# Miscellaneous.net
KiCad netlist of a schematic drawn in Altium Designer
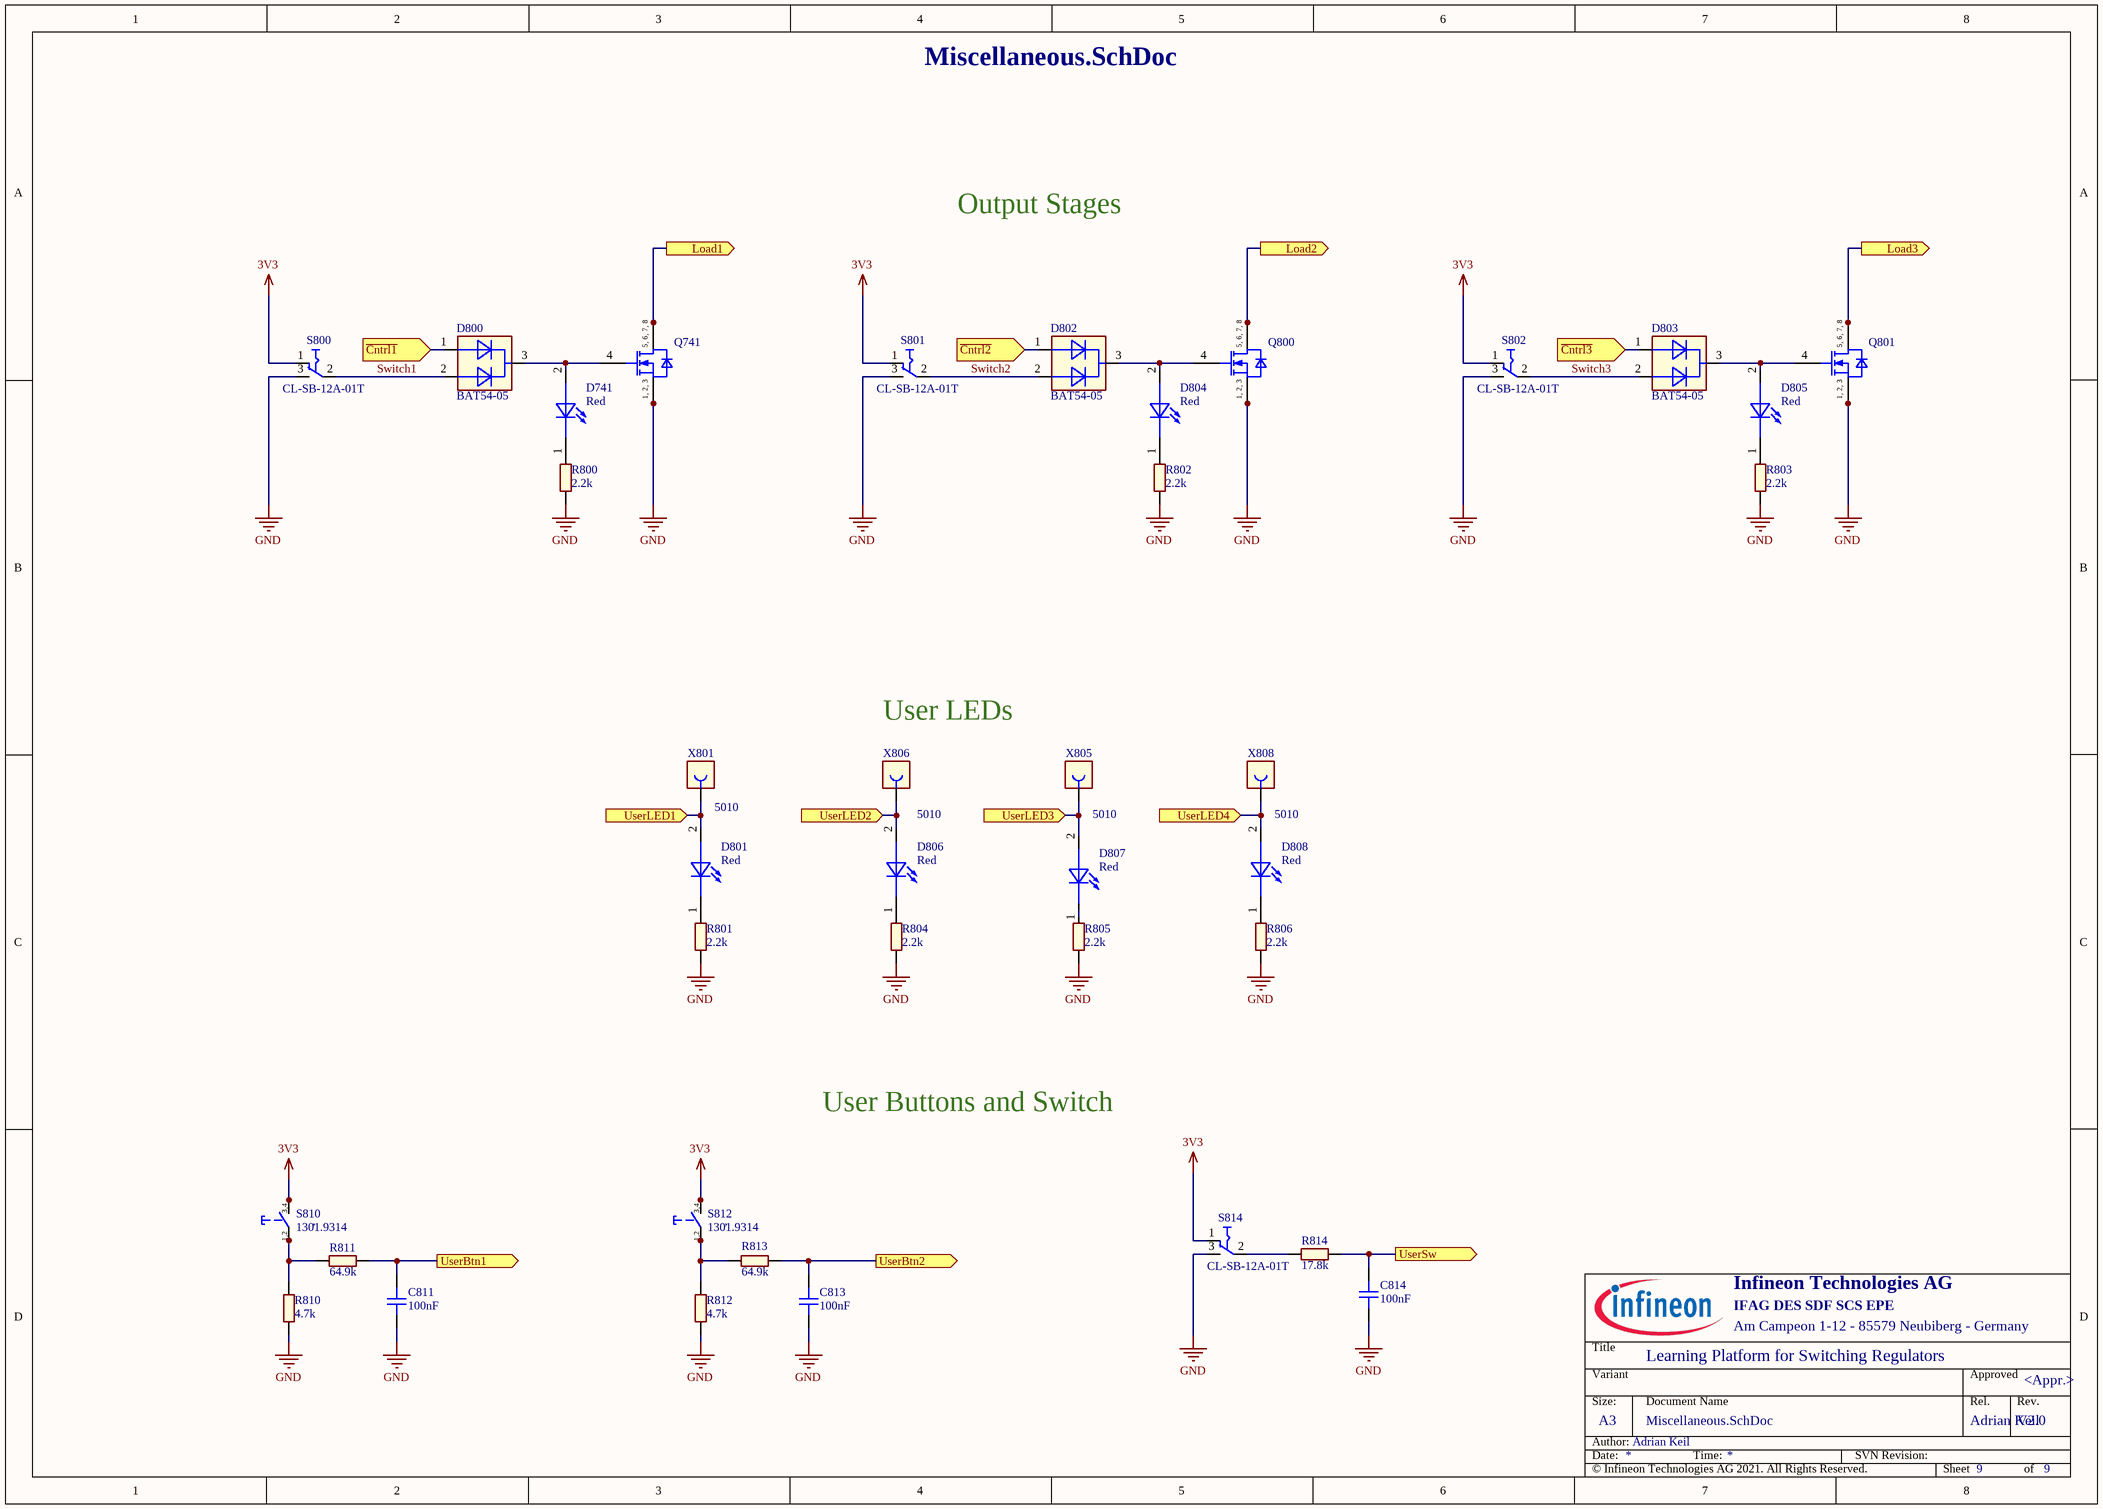
[diagram p0: Miscellaneous.SchDoc]

(export (version "E")
  (design (tool "Eeschema 10.0.6"))
  (components
    (comp (ref "C811")
      (value "100nF")
      (footprint "CAPC1608X90N-2")
      (description "CAP / CERA / 100nF / 50V / 10% / X7R (EIA) / -55°C to 125°C / 0603 / SMD / -")
      (fields (field (name "MANUFACTURER") "AVX"))
      (libsource (lib "PCBLibraryData") (part "CAP-SGL-STD-02P_00000001"))
    )
    (comp (ref "C813")
      (value "100nF")
      (footprint "CAPC1608X90N-2")
      (description "CAP / CERA / 100nF / 50V / 10% / X7R (EIA) / -55°C to 125°C / 0603 / SMD / -")
      (fields (field (name "MANUFACTURER") "AVX"))
      (libsource (lib "PCBLibraryData") (part "CAP-SGL-STD-02P_00000001"))
    )
    (comp (ref "C814")
      (value "100nF")
      (footprint "CAPC1608X90N-2")
      (description "CAP / CERA / 100nF / 50V / 10% / X7R (EIA) / -55°C to 125°C / 0603 / SMD / -")
      (fields (field (name "MANUFACTURER") "AVX"))
      (libsource (lib "PCBLibraryData") (part "CAP-SGL-STD-02P_00000001"))
    )
    (comp (ref "D741")
      (value "Red")
      (footprint "LEDSC160X80X80-2N-1")
      (description "WL-SMCW SMT Mono-color Chip LED Waterclear, Red,630nm")
      (fields (field (name "MANUFACTURER") "Wurth Elektronik"))
      (libsource (lib "PCBLibraryData") (part "d_led_a"))
    )
    (comp (ref "D800")
      (value "BAT54-05")
      (footprint "SOT95P240X110-3N-1-V")
      (description "Silicon Schottky Diode, LS(nH) 1.8, VR 30V")
      (fields
        (field (name "LEGACY PARTNUMBER") "IFX01401370")
        (field (name "MANUFACTURER") "Infineon Technologies")
      )
      (libsource (lib "PCBLibraryData") (part "d_dual_a1a2c3_3p"))
    )
    (comp (ref "D801")
      (value "Red")
      (footprint "LEDSC160X80X80-2N-1")
      (description "WL-SMCW SMT Mono-color Chip LED Waterclear, Red,630nm")
      (fields (field (name "MANUFACTURER") "Wurth Elektronik"))
      (libsource (lib "PCBLibraryData") (part "d_led_a"))
    )
    (comp (ref "D802")
      (value "BAT54-05")
      (footprint "SOT95P240X110-3N-1-V")
      (description "Silicon Schottky Diode, LS(nH) 1.8, VR 30V")
      (fields
        (field (name "LEGACY PARTNUMBER") "IFX01401370")
        (field (name "MANUFACTURER") "Infineon Technologies")
      )
      (libsource (lib "PCBLibraryData") (part "d_dual_a1a2c3_3p"))
    )
    (comp (ref "D803")
      (value "BAT54-05")
      (footprint "SOT95P240X110-3N-1-V")
      (description "Silicon Schottky Diode, LS(nH) 1.8, VR 30V")
      (fields
        (field (name "LEGACY PARTNUMBER") "IFX01401370")
        (field (name "MANUFACTURER") "Infineon Technologies")
      )
      (libsource (lib "PCBLibraryData") (part "d_dual_a1a2c3_3p"))
    )
    (comp (ref "D804")
      (value "Red")
      (footprint "LEDSC160X80X80-2N-1")
      (description "WL-SMCW SMT Mono-color Chip LED Waterclear, Red,630nm")
      (fields (field (name "MANUFACTURER") "Wurth Elektronik"))
      (libsource (lib "PCBLibraryData") (part "d_led_a"))
    )
    (comp (ref "D805")
      (value "Red")
      (footprint "LEDSC160X80X80-2N-1")
      (description "WL-SMCW SMT Mono-color Chip LED Waterclear, Red,630nm")
      (fields (field (name "MANUFACTURER") "Wurth Elektronik"))
      (libsource (lib "PCBLibraryData") (part "d_led_a"))
    )
    (comp (ref "D806")
      (value "Red")
      (footprint "LEDSC160X80X80-2N-1")
      (description "WL-SMCW SMT Mono-color Chip LED Waterclear, Red,630nm")
      (fields (field (name "MANUFACTURER") "Wurth Elektronik"))
      (libsource (lib "PCBLibraryData") (part "d_led_a"))
    )
    (comp (ref "D807")
      (value "Red")
      (footprint "LEDSC160X80X80-2N-1")
      (description "WL-SMCW SMT Mono-color Chip LED Waterclear, Red,630nm")
      (fields (field (name "MANUFACTURER") "Wurth Elektronik"))
      (libsource (lib "PCBLibraryData") (part "d_led_a"))
    )
    (comp (ref "D808")
      (value "Red")
      (footprint "LEDSC160X80X80-2N-1")
      (description "WL-SMCW SMT Mono-color Chip LED Waterclear, Red,630nm")
      (fields (field (name "MANUFACTURER") "Wurth Elektronik"))
      (libsource (lib "PCBLibraryData") (part "d_led_a"))
    )
    (comp (ref "Q741")
      (value "igfet_n_ch_enh_dio_1s2s3s4g5d6d7d8d_8p")
      (footprint "IFX-PG-TDSON-8-6-V")
      (description "OptiMOS Power MOSFET, 30V")
      (fields (field (name "MANUFACTURER") "Infineon Technologies"))
      (libsource (lib "PCBLibraryData") (part "igfet_n_ch_enh_dio_1s2s3s4g5d6d7d8d_8p"))
    )
    (comp (ref "Q800")
      (value "igfet_n_ch_enh_dio_1s2s3s4g5d6d7d8d_8p")
      (footprint "IFX-PG-TDSON-8-6-V")
      (description "OptiMOS Power MOSFET, 30V")
      (fields (field (name "MANUFACTURER") "Infineon Technologies"))
      (libsource (lib "PCBLibraryData") (part "igfet_n_ch_enh_dio_1s2s3s4g5d6d7d8d_8p"))
    )
    (comp (ref "Q801")
      (value "igfet_n_ch_enh_dio_1s2s3s4g5d6d7d8d_8p")
      (footprint "IFX-PG-TDSON-8-6-V")
      (description "OptiMOS Power MOSFET, 30V")
      (fields (field (name "MANUFACTURER") "Infineon Technologies"))
      (libsource (lib "PCBLibraryData") (part "igfet_n_ch_enh_dio_1s2s3s4g5d6d7d8d_8p"))
    )
    (comp (ref "R800")
      (value "2.2k")
      (footprint "RESC1609X50N")
      (description "RES / STD / 2.2k / 100mW / 1% / 100ppm/K / -55°C to 155°C / 0603 / SMD / -")
      (fields (field (name "LEGACY PARTNUMBER") "RES01801179") (field (name "MANUFACTURER") "Vishay"))
      (libsource (lib "") (part "RES-SGL-STD-02P_00000006_1"))
    )
    (comp (ref "R801")
      (value "2.2k")
      (footprint "RESC1609X50N")
      (description "RES / STD / 2.2k / 100mW / 1% / 100ppm/K / -55°C to 155°C / 0603 / SMD / -")
      (fields (field (name "LEGACY PARTNUMBER") "RES01801179") (field (name "MANUFACTURER") "Vishay"))
      (libsource (lib "") (part "RES-SGL-STD-02P_00000006_1"))
    )
    (comp (ref "R802")
      (value "2.2k")
      (footprint "RESC1609X50N")
      (description "RES / STD / 2.2k / 100mW / 1% / 100ppm/K / -55°C to 155°C / 0603 / SMD / -")
      (fields (field (name "LEGACY PARTNUMBER") "RES01801179") (field (name "MANUFACTURER") "Vishay"))
      (libsource (lib "") (part "RES-SGL-STD-02P_00000006_1"))
    )
    (comp (ref "R803")
      (value "2.2k")
      (footprint "RESC1609X50N")
      (description "RES / STD / 2.2k / 100mW / 1% / 100ppm/K / -55°C to 155°C / 0603 / SMD / -")
      (fields (field (name "LEGACY PARTNUMBER") "RES01801179") (field (name "MANUFACTURER") "Vishay"))
      (libsource (lib "") (part "RES-SGL-STD-02P_00000006_1"))
    )
    (comp (ref "R804")
      (value "2.2k")
      (footprint "RESC1609X50N")
      (description "RES / STD / 2.2k / 100mW / 1% / 100ppm/K / -55°C to 155°C / 0603 / SMD / -")
      (fields (field (name "LEGACY PARTNUMBER") "RES01801179") (field (name "MANUFACTURER") "Vishay"))
      (libsource (lib "") (part "RES-SGL-STD-02P_00000006_1"))
    )
    (comp (ref "R805")
      (value "2.2k")
      (footprint "RESC1609X50N")
      (description "RES / STD / 2.2k / 100mW / 1% / 100ppm/K / -55°C to 155°C / 0603 / SMD / -")
      (fields (field (name "LEGACY PARTNUMBER") "RES01801179") (field (name "MANUFACTURER") "Vishay"))
      (libsource (lib "") (part "RES-SGL-STD-02P_00000006_1"))
    )
    (comp (ref "R806")
      (value "2.2k")
      (footprint "RESC1609X50N")
      (description "RES / STD / 2.2k / 100mW / 1% / 100ppm/K / -55°C to 155°C / 0603 / SMD / -")
      (fields (field (name "LEGACY PARTNUMBER") "RES01801179") (field (name "MANUFACTURER") "Vishay"))
      (libsource (lib "") (part "RES-SGL-STD-02P_00000006_1"))
    )
    (comp (ref "R810")
      (value "4.7k")
      (footprint "RESC1609X55N")
      (description "RES / STD / 4.7k / 100mW / 1% / 100ppm/K / -55°C to 155°C / 1.60mm L X 0.85mm W X 0.55mm H / - / -")
      (fields (field (name "MANUFACTURER") "Panasonic"))
      (libsource (lib "") (part "RES-SGL-STD-02P_00000006_1"))
    )
    (comp (ref "R811")
      (value "64.9k")
      (footprint "RESC1608X60N")
      (fields (field (name "MANUFACTURER") "Multicomp"))
      (libsource (lib "PCBLibraryData") (part "RES-SGL-STD-02P_00000006"))
    )
    (comp (ref "R812")
      (value "4.7k")
      (footprint "RESC1609X55N")
      (description "RES / STD / 4.7k / 100mW / 1% / 100ppm/K / -55°C to 155°C / 1.60mm L X 0.85mm W X 0.55mm H / - / -")
      (fields (field (name "MANUFACTURER") "Panasonic"))
      (libsource (lib "") (part "RES-SGL-STD-02P_00000006_1"))
    )
    (comp (ref "R813")
      (value "64.9k")
      (footprint "RESC1608X60N")
      (fields (field (name "MANUFACTURER") "Multicomp"))
      (libsource (lib "PCBLibraryData") (part "RES-SGL-STD-02P_00000006"))
    )
    (comp (ref "R814")
      (value "17.8k")
      (footprint "RESC1608X60N")
      (fields (field (name "MANUFACTURER") "Multicomp"))
      (libsource (lib "PCBLibraryData") (part "RES-SGL-STD-02P_00000006"))
    )
    (comp (ref "S800")
      (value "CL-SB-12A-01T")
      (footprint "SW-SMD-CL-SB-12A-01T")
      (description "Slid Switch, 12V, 200mA")
      (fields (field (name "MANUFACTURER") "NIDEC COPAL ELECTRONICS, Inc."))
      (libsource (lib "PCBLibraryData") (part "sw_co213_3p"))
    )
    (comp (ref "S801")
      (value "CL-SB-12A-01T")
      (footprint "SW-SMD-CL-SB-12A-01T")
      (description "Slid Switch, 12V, 200mA")
      (fields (field (name "MANUFACTURER") "NIDEC COPAL ELECTRONICS, Inc."))
      (libsource (lib "PCBLibraryData") (part "sw_co213_3p"))
    )
    (comp (ref "S802")
      (value "CL-SB-12A-01T")
      (footprint "SW-SMD-CL-SB-12A-01T")
      (description "Slid Switch, 12V, 200mA")
      (fields (field (name "MANUFACTURER") "NIDEC COPAL ELECTRONICS, Inc."))
      (libsource (lib "PCBLibraryData") (part "sw_co213_3p"))
    )
    (comp (ref "S810")
      (value "1301.9314")
      (footprint "SW-SMD-1301.9314")
      (description "Pushbutton Tactile Switch, Single Pole Single Throw, 4 Pins")
      (fields (field (name "LEGACY PARTNUMBER") "CON01500305") (field (name "MANUFACTURER") "Schurter"))
      (libsource (lib "PCBLibraryData") (part "sw_sr_no12_34_4p"))
    )
    (comp (ref "S812")
      (value "1301.9314")
      (footprint "SW-SMD-1301.9314")
      (description "Pushbutton Tactile Switch, Single Pole Single Throw, 4 Pins")
      (fields (field (name "LEGACY PARTNUMBER") "CON01500305") (field (name "MANUFACTURER") "Schurter"))
      (libsource (lib "PCBLibraryData") (part "sw_sr_no12_34_4p"))
    )
    (comp (ref "S814")
      (value "CL-SB-12A-01T")
      (footprint "SW-SMD-CL-SB-12A-01T")
      (description "Slid Switch, 12V, 200mA")
      (fields (field (name "MANUFACTURER") "NIDEC COPAL ELECTRONICS, Inc."))
      (libsource (lib "PCBLibraryData") (part "sw_co213_3p"))
    )
    (comp (ref "X801")
      (value "5010")
      (footprint "CON-THT-TP-5010")
      (description "PC Test Point-Multipurpose THT, Red")
      (fields
        (field (name "LEGACY PARTNUMBER") "CON01500529")
        (field (name "MANUFACTURER") "Keystone Electronics Corp.")
      )
      (libsource (lib "PCBLibraryData") (part "connector_1_f"))
    )
    (comp (ref "X805")
      (value "5010")
      (footprint "CON-THT-TP-5010")
      (description "PC Test Point-Multipurpose THT, Red")
      (fields
        (field (name "LEGACY PARTNUMBER") "CON01500529")
        (field (name "MANUFACTURER") "Keystone Electronics Corp.")
      )
      (libsource (lib "PCBLibraryData") (part "connector_1_f"))
    )
    (comp (ref "X806")
      (value "5010")
      (footprint "CON-THT-TP-5010")
      (description "PC Test Point-Multipurpose THT, Red")
      (fields
        (field (name "LEGACY PARTNUMBER") "CON01500529")
        (field (name "MANUFACTURER") "Keystone Electronics Corp.")
      )
      (libsource (lib "PCBLibraryData") (part "connector_1_f"))
    )
    (comp (ref "X808")
      (value "5010")
      (footprint "CON-THT-TP-5010")
      (description "PC Test Point-Multipurpose THT, Red")
      (fields
        (field (name "LEGACY PARTNUMBER") "CON01500529")
        (field (name "MANUFACTURER") "Keystone Electronics Corp.")
      )
      (libsource (lib "PCBLibraryData") (part "connector_1_f"))
    )
  )
  (nets
    (net (code "1") (name "/Cntrl1") (class "Default")
      (node (ref "D800") (pin "1") (pinfunction "ANODE_1_1") (pintype "passive"))
    )
    (net (code "2") (name "/Cntrl2") (class "Default")
      (node (ref "D802") (pin "1") (pinfunction "ANODE_1_1") (pintype "passive"))
    )
    (net (code "3") (name "/Cntrl3") (class "Default")
      (node (ref "D803") (pin "1") (pinfunction "ANODE_1_1") (pintype "passive"))
    )
    (net (code "4") (name "/Load1") (class "Default")
      (node (ref "Q741") (pin "5") (pinfunction "DRAIN_5") (pintype "passive"))
      (node (ref "Q741") (pin "6") (pinfunction "DRAIN_6") (pintype "passive"))
      (node (ref "Q741") (pin "7") (pinfunction "DRAIN_7") (pintype "passive"))
      (node (ref "Q741") (pin "8") (pinfunction "DRAIN_8") (pintype "passive"))
    )
    (net (code "5") (name "/Load2") (class "Default")
      (node (ref "Q800") (pin "5") (pinfunction "DRAIN_5") (pintype "passive"))
      (node (ref "Q800") (pin "6") (pinfunction "DRAIN_6") (pintype "passive"))
      (node (ref "Q800") (pin "7") (pinfunction "DRAIN_7") (pintype "passive"))
      (node (ref "Q800") (pin "8") (pinfunction "DRAIN_8") (pintype "passive"))
    )
    (net (code "6") (name "/Load3") (class "Default")
      (node (ref "Q801") (pin "5") (pinfunction "DRAIN_5") (pintype "passive"))
      (node (ref "Q801") (pin "6") (pinfunction "DRAIN_6") (pintype "passive"))
      (node (ref "Q801") (pin "7") (pinfunction "DRAIN_7") (pintype "passive"))
      (node (ref "Q801") (pin "8") (pinfunction "DRAIN_8") (pintype "passive"))
    )
    (net (code "7") (name "/Switch1") (class "Default")
      (node (ref "D800") (pin "2") (pinfunction "ANODE_2_2") (pintype "passive"))
      (node (ref "S800") (pin "2") (pinfunction "2_2") (pintype "passive"))
    )
    (net (code "8") (name "/Switch2") (class "Default")
      (node (ref "D802") (pin "2") (pinfunction "ANODE_2_2") (pintype "passive"))
      (node (ref "S801") (pin "2") (pinfunction "2_2") (pintype "passive"))
    )
    (net (code "9") (name "/Switch3") (class "Default")
      (node (ref "D803") (pin "2") (pinfunction "ANODE_2_2") (pintype "passive"))
      (node (ref "S802") (pin "2") (pinfunction "2_2") (pintype "passive"))
    )
    (net (code "10") (name "/UserBtn1") (class "Default")
      (node (ref "C811") (pin "2") (pinfunction "2_2") (pintype "passive"))
      (node (ref "R811") (pin "2") (pinfunction "2_2") (pintype "passive"))
    )
    (net (code "11") (name "/UserBtn2") (class "Default")
      (node (ref "C813") (pin "2") (pinfunction "2_2") (pintype "passive"))
      (node (ref "R813") (pin "2") (pinfunction "2_2") (pintype "passive"))
    )
    (net (code "12") (name "/UserLED1") (class "Default")
      (node (ref "D801") (pin "2") (pinfunction "Anode_2") (pintype "passive"))
      (node (ref "X801") (pin "1") (pinfunction "1_1") (pintype "passive"))
    )
    (net (code "13") (name "/UserLED2") (class "Default")
      (node (ref "D806") (pin "2") (pinfunction "Anode_2") (pintype "passive"))
      (node (ref "X806") (pin "1") (pinfunction "1_1") (pintype "passive"))
    )
    (net (code "14") (name "/UserLED3") (class "Default")
      (node (ref "D807") (pin "2") (pinfunction "Anode_2") (pintype "passive"))
      (node (ref "X805") (pin "1") (pinfunction "1_1") (pintype "passive"))
    )
    (net (code "15") (name "/UserLED4") (class "Default")
      (node (ref "D808") (pin "2") (pinfunction "Anode_2") (pintype "passive"))
      (node (ref "X808") (pin "1") (pinfunction "1_1") (pintype "passive"))
    )
    (net (code "16") (name "/UserSw") (class "Default")
      (node (ref "C814") (pin "2") (pinfunction "2_2") (pintype "passive"))
      (node (ref "R814") (pin "2") (pinfunction "2_2") (pintype "passive"))
    )
    (net (code "17") (name "3V3") (class "Default")
      (node (ref "S800") (pin "1") (pinfunction "1_1") (pintype "passive"))
      (node (ref "S801") (pin "1") (pinfunction "1_1") (pintype "passive"))
      (node (ref "S802") (pin "1") (pinfunction "1_1") (pintype "passive"))
      (node (ref "S810") (pin "3") (pinfunction "3_3") (pintype "passive"))
      (node (ref "S810") (pin "4") (pinfunction "4_4") (pintype "passive"))
      (node (ref "S812") (pin "3") (pinfunction "3_3") (pintype "passive"))
      (node (ref "S812") (pin "4") (pinfunction "4_4") (pintype "passive"))
      (node (ref "S814") (pin "1") (pinfunction "1_1") (pintype "passive"))
    )
    (net (code "18") (name "GND") (class "Default")
      (node (ref "C811") (pin "1") (pinfunction "1_1") (pintype "passive"))
      (node (ref "C813") (pin "1") (pinfunction "1_1") (pintype "passive"))
      (node (ref "C814") (pin "1") (pinfunction "1_1") (pintype "passive"))
      (node (ref "Q741") (pin "1") (pinfunction "SOURCE_1") (pintype "passive"))
      (node (ref "Q741") (pin "2") (pinfunction "SOURCE_2") (pintype "passive"))
      (node (ref "Q741") (pin "3") (pinfunction "SOURCE_3") (pintype "passive"))
      (node (ref "Q800") (pin "1") (pinfunction "SOURCE_1") (pintype "passive"))
      (node (ref "Q800") (pin "2") (pinfunction "SOURCE_2") (pintype "passive"))
      (node (ref "Q800") (pin "3") (pinfunction "SOURCE_3") (pintype "passive"))
      (node (ref "Q801") (pin "1") (pinfunction "SOURCE_1") (pintype "passive"))
      (node (ref "Q801") (pin "2") (pinfunction "SOURCE_2") (pintype "passive"))
      (node (ref "Q801") (pin "3") (pinfunction "SOURCE_3") (pintype "passive"))
      (node (ref "R800") (pin "2") (pinfunction "2_2") (pintype "passive"))
      (node (ref "R801") (pin "2") (pinfunction "2_2") (pintype "passive"))
      (node (ref "R802") (pin "2") (pinfunction "2_2") (pintype "passive"))
      (node (ref "R803") (pin "2") (pinfunction "2_2") (pintype "passive"))
      (node (ref "R804") (pin "2") (pinfunction "2_2") (pintype "passive"))
      (node (ref "R805") (pin "2") (pinfunction "2_2") (pintype "passive"))
      (node (ref "R806") (pin "2") (pinfunction "2_2") (pintype "passive"))
      (node (ref "R810") (pin "2") (pinfunction "2_2") (pintype "passive"))
      (node (ref "R812") (pin "2") (pinfunction "2_2") (pintype "passive"))
      (node (ref "S800") (pin "3") (pinfunction "3_3") (pintype "passive"))
      (node (ref "S801") (pin "3") (pinfunction "3_3") (pintype "passive"))
      (node (ref "S802") (pin "3") (pinfunction "3_3") (pintype "passive"))
      (node (ref "S814") (pin "3") (pinfunction "3_3") (pintype "passive"))
    )
    (net (code "19") (name "Net-(D741-Anode)") (class "Default")
      (node (ref "D741") (pin "2") (pinfunction "Anode_2") (pintype "passive"))
      (node (ref "D800") (pin "3") (pinfunction "CATHODE_3") (pintype "passive"))
      (node (ref "Q741") (pin "4") (pinfunction "GATE_4") (pintype "passive"))
    )
    (net (code "20") (name "Net-(D741-Cathode)") (class "Default")
      (node (ref "D741") (pin "1") (pinfunction "Cathode_1") (pintype "passive"))
      (node (ref "R800") (pin "1") (pinfunction "1_1") (pintype "passive"))
    )
    (net (code "21") (name "Net-(D801-Cathode)") (class "Default")
      (node (ref "D801") (pin "1") (pinfunction "Cathode_1") (pintype "passive"))
      (node (ref "R801") (pin "1") (pinfunction "1_1") (pintype "passive"))
    )
    (net (code "22") (name "Net-(D802-CATHODE)") (class "Default")
      (node (ref "D802") (pin "3") (pinfunction "CATHODE_3") (pintype "passive"))
      (node (ref "D804") (pin "2") (pinfunction "Anode_2") (pintype "passive"))
      (node (ref "Q800") (pin "4") (pinfunction "GATE_4") (pintype "passive"))
    )
    (net (code "23") (name "Net-(D803-CATHODE)") (class "Default")
      (node (ref "D803") (pin "3") (pinfunction "CATHODE_3") (pintype "passive"))
      (node (ref "D805") (pin "2") (pinfunction "Anode_2") (pintype "passive"))
      (node (ref "Q801") (pin "4") (pinfunction "GATE_4") (pintype "passive"))
    )
    (net (code "24") (name "Net-(D804-Cathode)") (class "Default")
      (node (ref "D804") (pin "1") (pinfunction "Cathode_1") (pintype "passive"))
      (node (ref "R802") (pin "1") (pinfunction "1_1") (pintype "passive"))
    )
    (net (code "25") (name "Net-(D805-Cathode)") (class "Default")
      (node (ref "D805") (pin "1") (pinfunction "Cathode_1") (pintype "passive"))
      (node (ref "R803") (pin "1") (pinfunction "1_1") (pintype "passive"))
    )
    (net (code "26") (name "Net-(D806-Cathode)") (class "Default")
      (node (ref "D806") (pin "1") (pinfunction "Cathode_1") (pintype "passive"))
      (node (ref "R804") (pin "1") (pinfunction "1_1") (pintype "passive"))
    )
    (net (code "27") (name "Net-(D807-Cathode)") (class "Default")
      (node (ref "D807") (pin "1") (pinfunction "Cathode_1") (pintype "passive"))
      (node (ref "R805") (pin "1") (pinfunction "1_1") (pintype "passive"))
    )
    (net (code "28") (name "Net-(D808-Cathode)") (class "Default")
      (node (ref "D808") (pin "1") (pinfunction "Cathode_1") (pintype "passive"))
      (node (ref "R806") (pin "1") (pinfunction "1_1") (pintype "passive"))
    )
    (net (code "29") (name "Net-(R810-Pad1)") (class "Default")
      (node (ref "R810") (pin "1") (pinfunction "1_1") (pintype "passive"))
      (node (ref "R811") (pin "1") (pinfunction "1_1") (pintype "passive"))
      (node (ref "S810") (pin "1") (pinfunction "1_1") (pintype "passive"))
      (node (ref "S810") (pin "2") (pinfunction "2_2") (pintype "passive"))
    )
    (net (code "30") (name "Net-(R812-Pad1)") (class "Default")
      (node (ref "R812") (pin "1") (pinfunction "1_1") (pintype "passive"))
      (node (ref "R813") (pin "1") (pinfunction "1_1") (pintype "passive"))
      (node (ref "S812") (pin "1") (pinfunction "1_1") (pintype "passive"))
      (node (ref "S812") (pin "2") (pinfunction "2_2") (pintype "passive"))
    )
    (net (code "31") (name "Net-(R814-Pad1)") (class "Default")
      (node (ref "R814") (pin "1") (pinfunction "1_1") (pintype "passive"))
      (node (ref "S814") (pin "2") (pinfunction "2_2") (pintype "passive"))
    )
  )
)
